# WL-FRONT.net
KiCad netlist of a schematic drawn in Altium Designer
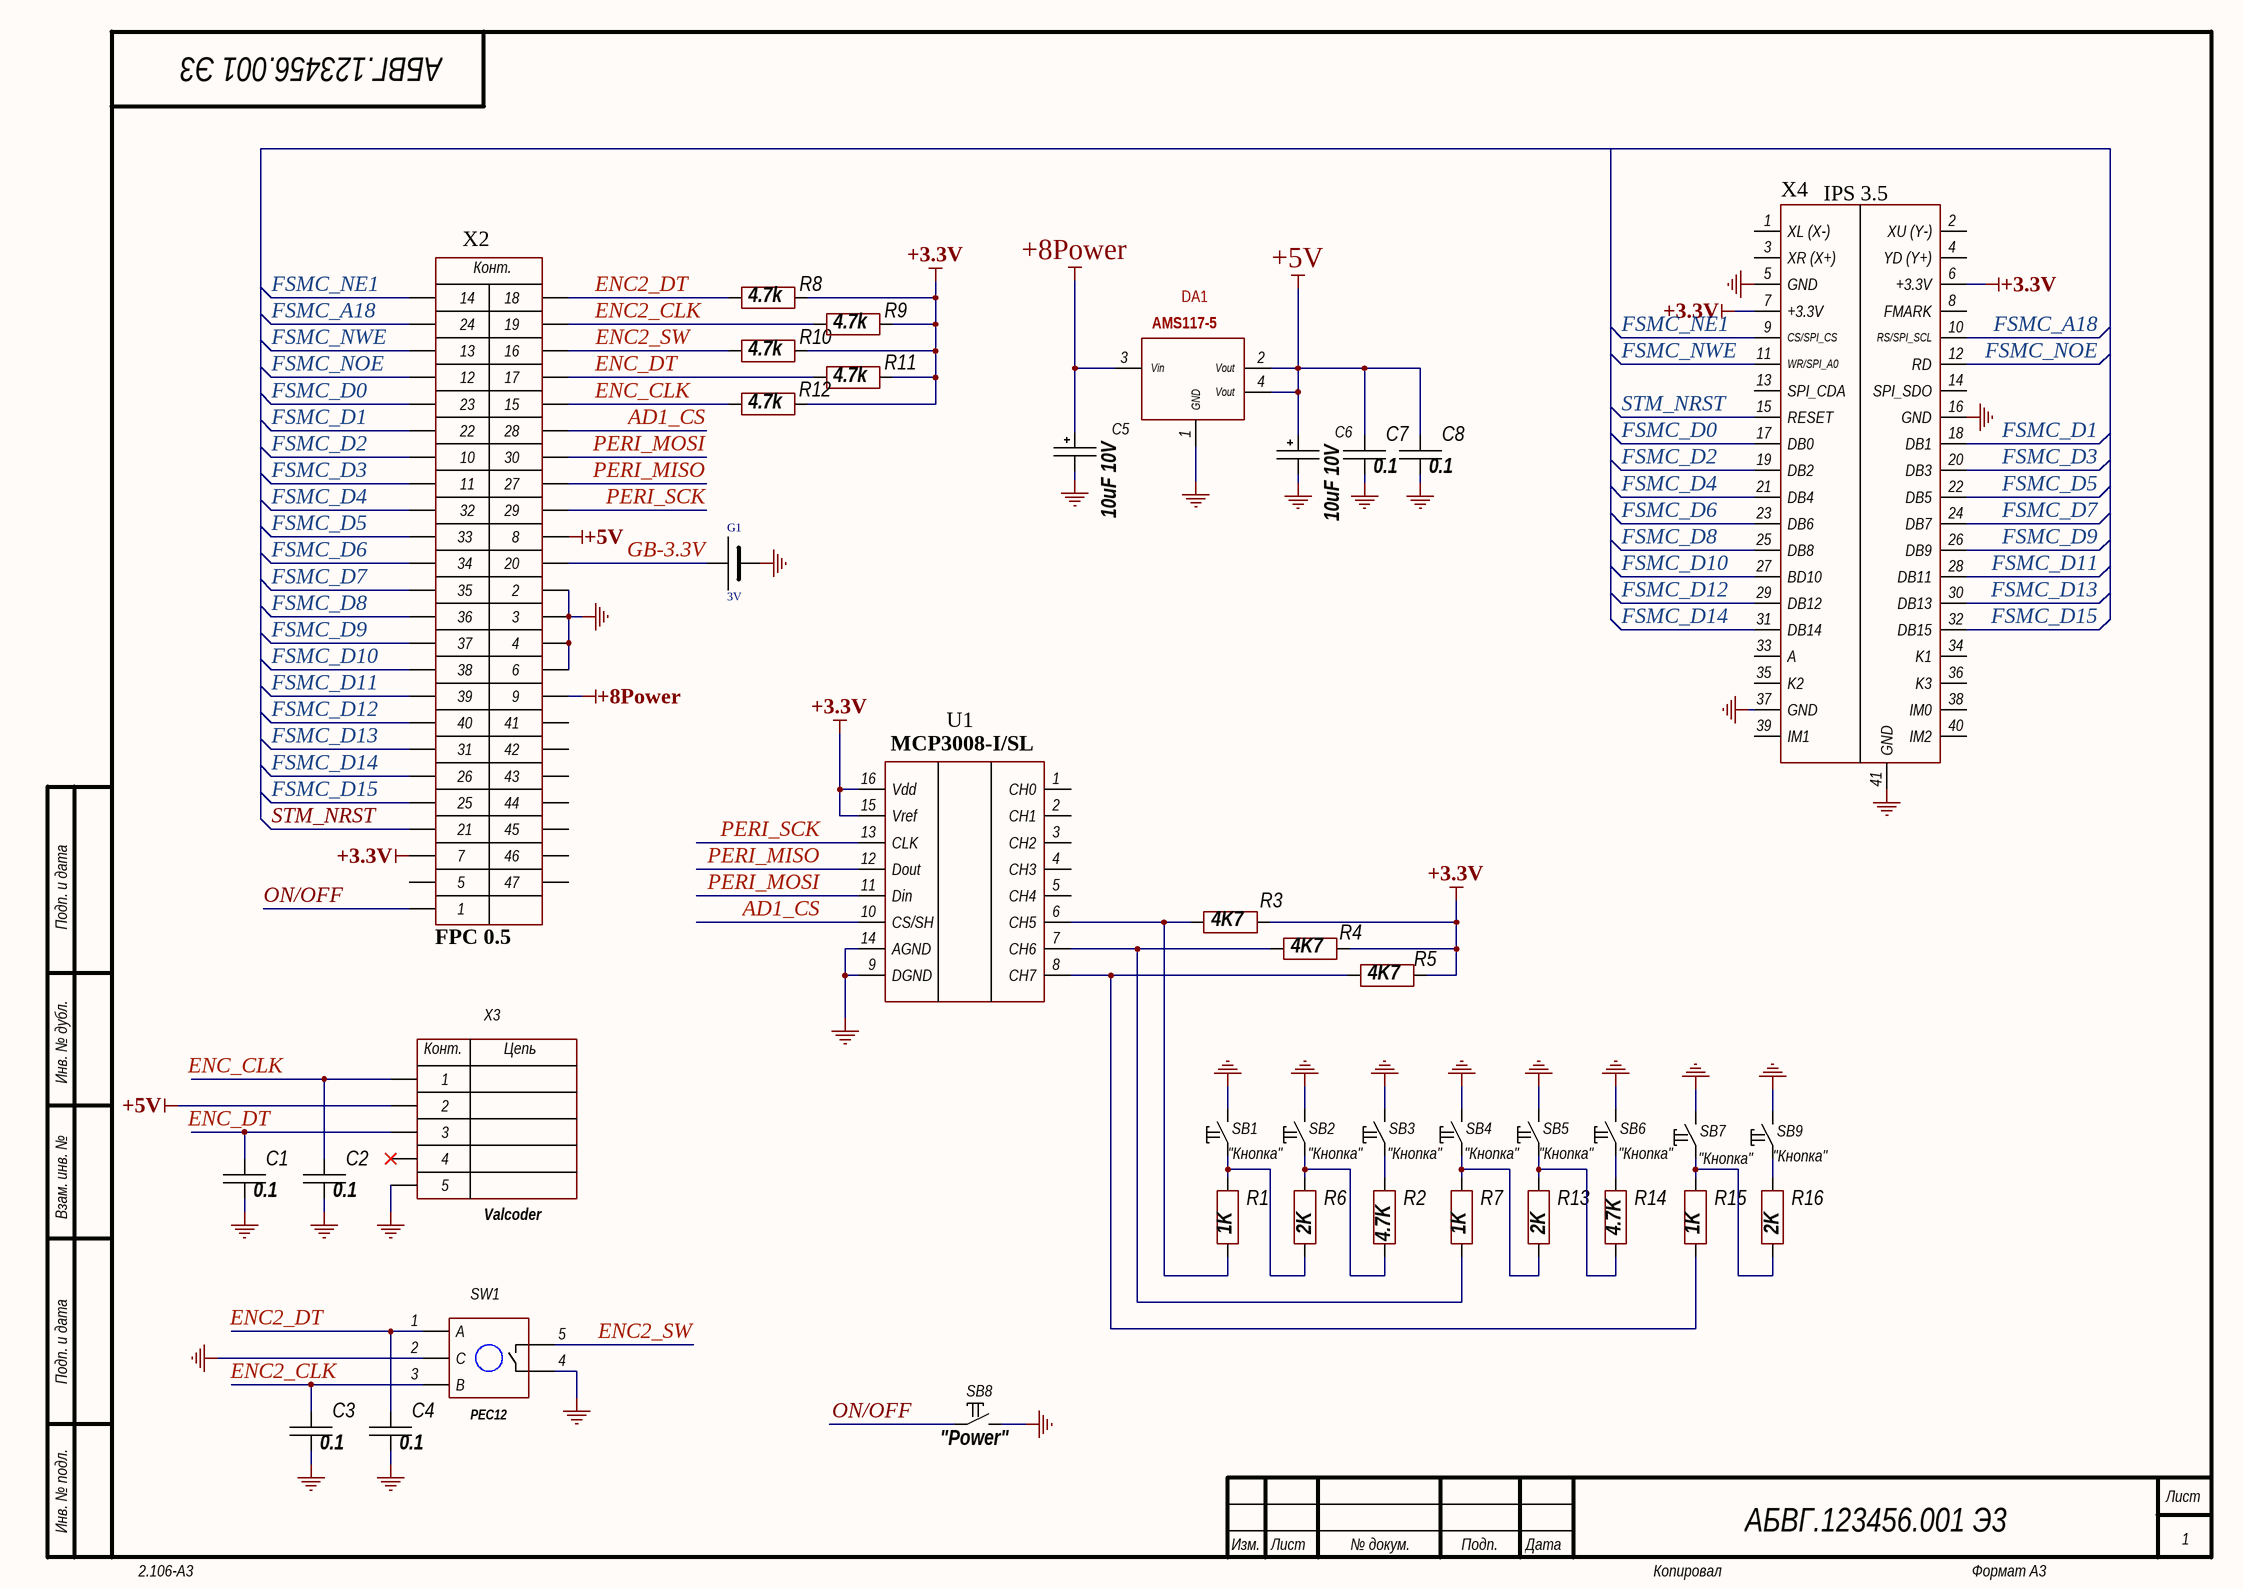
[diagram p0: WL-FRONT.SchDoc]

(export (version "E")
  (design (tool "Eeschema 10.0.6"))
  (components
    (comp (ref "C1")
      (value "0.1")
      (footprint "standard:CH0805C")
      (libsource (lib "Discrete") (part "Capacitor"))
    )
    (comp (ref "C2")
      (value "0.1")
      (footprint "standard:CH0805C")
      (libsource (lib "Discrete") (part "Capacitor"))
    )
    (comp (ref "C3")
      (value "0.1")
      (footprint "standard:CH0805C")
      (libsource (lib "Discrete") (part "Capacitor"))
    )
    (comp (ref "C4")
      (value "0.1")
      (footprint "standard:CH0805C")
      (libsource (lib "Discrete") (part "Capacitor"))
    )
    (comp (ref "C5")
      (value "10uF 10V")
      (footprint "standard:TANTAL_B")
      (libsource (lib "Discrete") (part "TantalCap"))
    )
    (comp (ref "C6")
      (value "10uF 10V")
      (footprint "standard:TANTAL_B")
      (libsource (lib "Discrete") (part "TantalCap"))
    )
    (comp (ref "C7")
      (value "0.1")
      (footprint "standard:CH0805C")
      (libsource (lib "Discrete") (part "Capacitor"))
    )
    (comp (ref "C8")
      (value "0.1")
      (footprint "standard:CH0805C")
      (libsource (lib "Discrete") (part "Capacitor"))
    )
    (comp (ref "DA1") (value "AMS117-5") (footprint "SOT223") (libsource (lib "Analog") (part "AMS117")))
    (comp (ref "G1")
      (value "3V")
      (footprint "BAT: CH224-2032")
      (libsource (lib "Connectors") (part "POWER_BAT"))
    )
    (comp (ref "R1") (value "1K") (footprint "standard:CH0805R") (libsource (lib "") (part "Resistor_2")))
    (comp (ref "R2") (value "4.7K") (footprint "standard:CH0805R") (libsource (lib "") (part "Resistor_2")))
    (comp (ref "R3")
      (value "4K7")
      (footprint "standard:CH0805R")
      (libsource (lib "Discrete") (part "Resistor"))
    )
    (comp (ref "R4") (value "4K7") (footprint "standard:CH0805R") (libsource (lib "") (part "Resistor_3")))
    (comp (ref "R5")
      (value "4K7")
      (footprint "standard:CH0805R")
      (libsource (lib "Discrete") (part "Resistor"))
    )
    (comp (ref "R6") (value "2K") (footprint "standard:CH0805R") (libsource (lib "") (part "Resistor_2")))
    (comp (ref "R7") (value "1K") (footprint "standard:CH0805R") (libsource (lib "") (part "Resistor_2")))
    (comp (ref "R8") (value "4.7k") (footprint "standard:CH0805R") (libsource (lib "") (part "Resistor_1")))
    (comp (ref "R9") (value "4.7k") (footprint "standard:CH0805R") (libsource (lib "") (part "Resistor_1")))
    (comp (ref "R10") (value "4.7k") (footprint "standard:CH0805R") (libsource (lib "") (part "Resistor_1")))
    (comp (ref "R11") (value "4.7k") (footprint "standard:CH0805R") (libsource (lib "") (part "Resistor_1")))
    (comp (ref "R12") (value "4.7k") (footprint "standard:CH0805R") (libsource (lib "") (part "Resistor_1")))
    (comp (ref "R13") (value "2K") (footprint "standard:CH0805R") (libsource (lib "") (part "Resistor_2")))
    (comp (ref "R14") (value "4.7K") (footprint "standard:CH0805R") (libsource (lib "") (part "Resistor_2")))
    (comp (ref "R15") (value "1K") (footprint "standard:CH0805R") (libsource (lib "") (part "Resistor_2")))
    (comp (ref "R16") (value "2K") (footprint "standard:CH0805R") (libsource (lib "") (part "Resistor_2")))
    (comp (ref "SB1")
      (value "\"Кнопка\"")
      (footprint "BUT: 6X6_SMD1")
      (description "6x6 mm")
      (libsource (lib "Connectors") (part "Tactile switches"))
    )
    (comp (ref "SB2")
      (value "\"Кнопка\"")
      (footprint "custom:BUT: 6x6 SMD")
      (description "6x6 mm")
      (libsource (lib "Connectors") (part "Tactile switches"))
    )
    (comp (ref "SB3")
      (value "\"Кнопка\"")
      (footprint "custom:BUT: 6x6 SMD")
      (description "6x6 mm")
      (libsource (lib "Connectors") (part "Tactile switches"))
    )
    (comp (ref "SB4")
      (value "\"Кнопка\"")
      (footprint "custom:BUT: 6x6 SMD")
      (description "6x6 mm")
      (libsource (lib "Connectors") (part "Tactile switches"))
    )
    (comp (ref "SB5")
      (value "\"Кнопка\"")
      (footprint "custom:BUT: 6x6 SMD")
      (description "6x6 mm")
      (libsource (lib "Connectors") (part "Tactile switches"))
    )
    (comp (ref "SB6")
      (value "\"Кнопка\"")
      (footprint "custom:BUT: 6x6 SMD")
      (description "6x6 mm")
      (libsource (lib "Connectors") (part "Tactile switches"))
    )
    (comp (ref "SB7")
      (value "\"Кнопка\"")
      (footprint "custom:BUT: 6x6 SMD")
      (description "6x6 mm")
      (libsource (lib "Connectors") (part "Tactile switches"))
    )
    (comp (ref "SB8")
      (value "\"Power\"")
      (footprint "custom:BUT: 6x6")
      (description "6x6 mm")
      (libsource (lib "Connectors") (part "Tactile switches"))
    )
    (comp (ref "SB9")
      (value "\"Кнопка\"")
      (footprint "custom:BUT: 6x6 SMD")
      (description "6x6 mm")
      (libsource (lib "Connectors") (part "Tactile switches"))
    )
    (comp (ref "SW1")
      (value "PEC12")
      (footprint "Valkoder-m2")
      (description "Encoder")
      (libsource (lib "Connectors") (part "PEC12"))
    )
    (comp (ref "U1")
      (value "MCP3008-I/SL")
      (footprint "16-SOIC")
      (libsource (lib "Digital") (part "MCP3008-I/SL"))
    )
    (comp (ref "X2")
      (value "FPC 0.5")
      (footprint "CON: PBD2x20")
      (libsource (lib "Connectors") (part "FPC-45-0.5"))
    )
    (comp (ref "X3")
      (value "Valcoder")
      (footprint "custom:CON: PLS-5")
      (libsource (lib "Connectors") (part "5-Connector"))
    )
    (comp (ref "X4")
      (value "IPS 3.5")
      (footprint "IPS 3.5 ILI9481")
      (libsource (lib "Digital") (part "LCD-IPS 3.5"))
    )
  )
  (nets
    (net (code "1") (name "+3.3V") (class "Default")
      (node (ref "R10") (pin "1") (pinfunction "1_1") (pintype "passive"))
      (node (ref "R11") (pin "1") (pinfunction "1_1") (pintype "passive"))
      (node (ref "R12") (pin "1") (pinfunction "1_1") (pintype "passive"))
      (node (ref "R3") (pin "2") (pinfunction "2_2") (pintype "passive"))
      (node (ref "R4") (pin "2") (pinfunction "2_2") (pintype "passive"))
      (node (ref "R5") (pin "2") (pinfunction "2_2") (pintype "passive"))
      (node (ref "R8") (pin "1") (pinfunction "1_1") (pintype "passive"))
      (node (ref "R9") (pin "1") (pinfunction "1_1") (pintype "passive"))
      (node (ref "U1") (pin "15") (pinfunction "Vref_15") (pintype "passive"))
      (node (ref "U1") (pin "16") (pinfunction "Vdd_16") (pintype "passive"))
      (node (ref "X2") (pin "7") (pinfunction "7_7") (pintype "power_in"))
      (node (ref "X4") (pin "6") (pinfunction "+3.3V_6") (pintype "passive"))
      (node (ref "X4") (pin "7") (pinfunction "+3.3V_7") (pintype "passive"))
    )
    (net (code "2") (name "+5V") (class "Default")
      (node (ref "C6") (pin "1") (pinfunction "1_1") (pintype "power_in"))
      (node (ref "C7") (pin "1") (pinfunction "1_1") (pintype "power_in"))
      (node (ref "C8") (pin "1") (pinfunction "1_1") (pintype "power_in"))
      (node (ref "DA1") (pin "2") (pinfunction "Vout_2") (pintype "passive"))
      (node (ref "DA1") (pin "4") (pinfunction "Vout_4") (pintype "passive"))
      (node (ref "X2") (pin "8") (pinfunction "8_8") (pintype "power_in"))
      (node (ref "X3") (pin "2") (pinfunction "2_2") (pintype "passive"))
    )
    (net (code "3") (name "+8Power") (class "Default")
      (node (ref "C5") (pin "1") (pinfunction "1_1") (pintype "power_in"))
      (node (ref "DA1") (pin "3") (pinfunction "Vin_3") (pintype "passive"))
      (node (ref "X2") (pin "9") (pinfunction "9_9") (pintype "power_in"))
    )
    (net (code "4") (name "/AD1_CS") (class "Default")
      (node (ref "U1") (pin "10") (pinfunction "CS/SH_10") (pintype "passive"))
      (node (ref "X2") (pin "28") (pinfunction "28_28") (pintype "power_in"))
    )
    (net (code "5") (name "/ENC2_CLK") (class "Default")
      (node (ref "C3") (pin "1") (pinfunction "1_1") (pintype "power_in"))
      (node (ref "R9") (pin "2") (pinfunction "2_2") (pintype "passive"))
      (node (ref "SW1") (pin "3") (pinfunction "B_3") (pintype "passive"))
      (node (ref "X2") (pin "19") (pinfunction "19_19") (pintype "power_in"))
    )
    (net (code "6") (name "/ENC2_DT") (class "Default")
      (node (ref "C4") (pin "1") (pinfunction "1_1") (pintype "power_in"))
      (node (ref "R8") (pin "2") (pinfunction "2_2") (pintype "passive"))
      (node (ref "SW1") (pin "1") (pinfunction "A_1") (pintype "passive"))
      (node (ref "X2") (pin "18") (pinfunction "18_18") (pintype "power_in"))
    )
    (net (code "7") (name "/ENC2_SW") (class "Default")
      (node (ref "R10") (pin "2") (pinfunction "2_2") (pintype "passive"))
      (node (ref "SW1") (pin "5") (pinfunction "5_5") (pintype "passive"))
      (node (ref "X2") (pin "16") (pinfunction "16_16") (pintype "power_in"))
    )
    (net (code "8") (name "/ENC_CLK") (class "Default")
      (node (ref "C2") (pin "1") (pinfunction "1_1") (pintype "power_in"))
      (node (ref "R12") (pin "2") (pinfunction "2_2") (pintype "passive"))
      (node (ref "X2") (pin "15") (pinfunction "15_15") (pintype "power_in"))
      (node (ref "X3") (pin "1") (pinfunction "1_1") (pintype "passive"))
    )
    (net (code "9") (name "/ENC_DT") (class "Default")
      (node (ref "C1") (pin "1") (pinfunction "1_1") (pintype "power_in"))
      (node (ref "R11") (pin "2") (pinfunction "2_2") (pintype "passive"))
      (node (ref "X2") (pin "17") (pinfunction "17_17") (pintype "power_in"))
      (node (ref "X3") (pin "3") (pinfunction "3_3") (pintype "power_in"))
    )
    (net (code "10") (name "/FSMC_A18") (class "Default")
      (node (ref "X2") (pin "24") (pinfunction "24_24") (pintype "passive"))
      (node (ref "X4") (pin "10") (pinfunction "RS/SPI_SCL_10") (pintype "passive"))
    )
    (net (code "11") (name "/FSMC_D0") (class "Default")
      (node (ref "X2") (pin "23") (pinfunction "23_23") (pintype "power_in"))
      (node (ref "X4") (pin "17") (pinfunction "DB0_17") (pintype "passive"))
    )
    (net (code "12") (name "/FSMC_D1") (class "Default")
      (node (ref "X2") (pin "22") (pinfunction "22_22") (pintype "power_in"))
      (node (ref "X4") (pin "18") (pinfunction "DB1_18") (pintype "passive"))
    )
    (net (code "13") (name "/FSMC_D2") (class "Default")
      (node (ref "X2") (pin "10") (pinfunction "10_10") (pintype "power_in"))
      (node (ref "X4") (pin "19") (pinfunction "DB2_19") (pintype "passive"))
    )
    (net (code "14") (name "/FSMC_D3") (class "Default")
      (node (ref "X2") (pin "11") (pinfunction "11_11") (pintype "power_in"))
      (node (ref "X4") (pin "20") (pinfunction "DB3_20") (pintype "passive"))
    )
    (net (code "15") (name "/FSMC_D4") (class "Default")
      (node (ref "X2") (pin "32") (pinfunction "32_32") (pintype "power_in"))
      (node (ref "X4") (pin "21") (pinfunction "DB4_21") (pintype "passive"))
    )
    (net (code "16") (name "/FSMC_D5") (class "Default")
      (node (ref "X2") (pin "33") (pinfunction "33_33") (pintype "power_in"))
      (node (ref "X4") (pin "22") (pinfunction "DB5_22") (pintype "passive"))
    )
    (net (code "17") (name "/FSMC_D6") (class "Default")
      (node (ref "X2") (pin "34") (pinfunction "34_34") (pintype "power_in"))
      (node (ref "X4") (pin "23") (pinfunction "DB6_23") (pintype "passive"))
    )
    (net (code "18") (name "/FSMC_D7") (class "Default")
      (node (ref "X2") (pin "35") (pinfunction "35_35") (pintype "power_in"))
      (node (ref "X4") (pin "24") (pinfunction "DB7_24") (pintype "passive"))
    )
    (net (code "19") (name "/FSMC_D8") (class "Default")
      (node (ref "X2") (pin "36") (pinfunction "36_36") (pintype "power_in"))
      (node (ref "X4") (pin "25") (pinfunction "DB8_25") (pintype "passive"))
    )
    (net (code "20") (name "/FSMC_D9") (class "Default")
      (node (ref "X2") (pin "37") (pinfunction "37_37") (pintype "power_in"))
      (node (ref "X4") (pin "26") (pinfunction "DB9_26") (pintype "passive"))
    )
    (net (code "21") (name "/FSMC_D10") (class "Default")
      (node (ref "X2") (pin "38") (pinfunction "38_38") (pintype "power_in"))
      (node (ref "X4") (pin "27") (pinfunction "BD10_27") (pintype "passive"))
    )
    (net (code "22") (name "/FSMC_D11") (class "Default")
      (node (ref "X2") (pin "39") (pinfunction "39_39") (pintype "power_in"))
      (node (ref "X4") (pin "28") (pinfunction "DB11_28") (pintype "passive"))
    )
    (net (code "23") (name "/FSMC_D12") (class "Default")
      (node (ref "X2") (pin "40") (pinfunction "40_40") (pintype "power_in"))
      (node (ref "X4") (pin "29") (pinfunction "DB12_29") (pintype "passive"))
    )
    (net (code "24") (name "/FSMC_D13") (class "Default")
      (node (ref "X2") (pin "31") (pinfunction "31_31") (pintype "power_in"))
      (node (ref "X4") (pin "30") (pinfunction "DB13_30") (pintype "passive"))
    )
    (net (code "25") (name "/FSMC_D14") (class "Default")
      (node (ref "X2") (pin "26") (pinfunction "26_26") (pintype "power_in"))
      (node (ref "X4") (pin "31") (pinfunction "DB14_31") (pintype "passive"))
    )
    (net (code "26") (name "/FSMC_D15") (class "Default")
      (node (ref "X2") (pin "25") (pinfunction "25_25") (pintype "power_in"))
      (node (ref "X4") (pin "32") (pinfunction "DB15_32") (pintype "passive"))
    )
    (net (code "27") (name "/FSMC_NE1") (class "Default")
      (node (ref "X2") (pin "14") (pinfunction "14_14") (pintype "passive"))
      (node (ref "X4") (pin "9") (pinfunction "CS/SPI_CS_9") (pintype "passive"))
    )
    (net (code "28") (name "/FSMC_NOE") (class "Default")
      (node (ref "X2") (pin "12") (pinfunction "12_12") (pintype "power_in"))
      (node (ref "X4") (pin "12") (pinfunction "RD_12") (pintype "passive"))
    )
    (net (code "29") (name "/FSMC_NWE") (class "Default")
      (node (ref "X2") (pin "13") (pinfunction "13_13") (pintype "power_in"))
      (node (ref "X4") (pin "11") (pinfunction "WR/SPI_A0_11") (pintype "passive"))
    )
    (net (code "30") (name "/GB-3.3V") (class "Default")
      (node (ref "G1") (pin "1") (pinfunction "0_1") (pintype "passive"))
      (node (ref "X2") (pin "20") (pinfunction "20_20") (pintype "power_in"))
    )
    (net (code "31") (name "/ON{slash}OFF") (class "Default")
      (node (ref "SB8") (pin "1") (pinfunction "1_1") (pintype "passive"))
      (node (ref "X2") (pin "1") (pinfunction "1_1") (pintype "power_in"))
    )
    (net (code "32") (name "/PERI_MISO") (class "Default")
      (node (ref "U1") (pin "12") (pinfunction "Dout_12") (pintype "passive"))
      (node (ref "X2") (pin "27") (pinfunction "27_27") (pintype "power_in"))
    )
    (net (code "33") (name "/PERI_MOSI") (class "Default")
      (node (ref "U1") (pin "11") (pinfunction "Din_11") (pintype "passive"))
      (node (ref "X2") (pin "30") (pinfunction "30_30") (pintype "power_in"))
    )
    (net (code "34") (name "/PERI_SCK") (class "Default")
      (node (ref "U1") (pin "13") (pinfunction "CLK_13") (pintype "passive"))
      (node (ref "X2") (pin "29") (pinfunction "29_29") (pintype "power_in"))
    )
    (net (code "35") (name "/STM_NRST") (class "Default")
      (node (ref "X2") (pin "21") (pinfunction "21_21") (pintype "power_in"))
      (node (ref "X4") (pin "15") (pinfunction "RESET_15") (pintype "passive"))
    )
    (net (code "36") (name "GND") (class "Default")
      (node (ref "C1") (pin "2") (pinfunction "2_2") (pintype "power_in"))
      (node (ref "C2") (pin "2") (pinfunction "2_2") (pintype "power_in"))
      (node (ref "C3") (pin "2") (pinfunction "2_2") (pintype "power_in"))
      (node (ref "C4") (pin "2") (pinfunction "2_2") (pintype "power_in"))
      (node (ref "C5") (pin "2") (pinfunction "2_2") (pintype "power_in"))
      (node (ref "C6") (pin "2") (pinfunction "2_2") (pintype "power_in"))
      (node (ref "C7") (pin "2") (pinfunction "2_2") (pintype "power_in"))
      (node (ref "C8") (pin "2") (pinfunction "2_2") (pintype "power_in"))
      (node (ref "DA1") (pin "1") (pinfunction "GND_1") (pintype "passive"))
      (node (ref "G1") (pin "2") (pinfunction "1_2") (pintype "passive"))
      (node (ref "SB1") (pin "2") (pinfunction "2_2") (pintype "passive"))
      (node (ref "SB2") (pin "2") (pinfunction "2_2") (pintype "passive"))
      (node (ref "SB3") (pin "2") (pinfunction "2_2") (pintype "passive"))
      (node (ref "SB4") (pin "2") (pinfunction "2_2") (pintype "passive"))
      (node (ref "SB5") (pin "2") (pinfunction "2_2") (pintype "passive"))
      (node (ref "SB6") (pin "2") (pinfunction "2_2") (pintype "passive"))
      (node (ref "SB7") (pin "2") (pinfunction "2_2") (pintype "passive"))
      (node (ref "SB8") (pin "2") (pinfunction "2_2") (pintype "passive"))
      (node (ref "SB9") (pin "2") (pinfunction "2_2") (pintype "passive"))
      (node (ref "SW1") (pin "2") (pinfunction "C_2") (pintype "passive"))
      (node (ref "SW1") (pin "4") (pinfunction "4_4") (pintype "passive"))
      (node (ref "U1") (pin "14") (pinfunction "AGND_14") (pintype "passive"))
      (node (ref "U1") (pin "9") (pinfunction "DGND_9") (pintype "passive"))
      (node (ref "X2") (pin "2") (pinfunction "2_2") (pintype "power_in"))
      (node (ref "X2") (pin "3") (pinfunction "3_3") (pintype "power_in"))
      (node (ref "X2") (pin "4") (pinfunction "4_4") (pintype "power_in"))
      (node (ref "X2") (pin "6") (pinfunction "6_6") (pintype "power_in"))
      (node (ref "X3") (pin "5") (pinfunction "5_5") (pintype "power_in"))
      (node (ref "X4") (pin "16") (pinfunction "GND_16") (pintype "passive"))
      (node (ref "X4") (pin "37") (pinfunction "GND_37") (pintype "passive"))
      (node (ref "X4") (pin "41") (pinfunction "GND_41") (pintype "passive"))
      (node (ref "X4") (pin "5") (pinfunction "GND_5") (pintype "passive"))
    )
    (net (code "37") (name "Net-(R1-Pad2)") (class "Default")
      (node (ref "R1") (pin "2") (pinfunction "2_2") (pintype "passive"))
      (node (ref "R6") (pin "1") (pinfunction "1_1") (pintype "passive"))
      (node (ref "SB1") (pin "1") (pinfunction "1_1") (pintype "passive"))
    )
    (net (code "38") (name "Net-(R2-Pad1)") (class "Default")
      (node (ref "R2") (pin "1") (pinfunction "1_1") (pintype "passive"))
      (node (ref "R6") (pin "2") (pinfunction "2_2") (pintype "passive"))
      (node (ref "SB2") (pin "1") (pinfunction "1_1") (pintype "passive"))
    )
    (net (code "39") (name "Net-(R2-Pad2)") (class "Default")
      (node (ref "R2") (pin "2") (pinfunction "2_2") (pintype "passive"))
      (node (ref "SB3") (pin "1") (pinfunction "1_1") (pintype "passive"))
    )
    (net (code "40") (name "Net-(R13-Pad1)") (class "Default")
      (node (ref "R13") (pin "1") (pinfunction "1_1") (pintype "passive"))
      (node (ref "R7") (pin "2") (pinfunction "2_2") (pintype "passive"))
      (node (ref "SB4") (pin "1") (pinfunction "1_1") (pintype "passive"))
    )
    (net (code "41") (name "Net-(R13-Pad2)") (class "Default")
      (node (ref "R13") (pin "2") (pinfunction "2_2") (pintype "passive"))
      (node (ref "R14") (pin "1") (pinfunction "1_1") (pintype "passive"))
      (node (ref "SB5") (pin "1") (pinfunction "1_1") (pintype "passive"))
    )
    (net (code "42") (name "Net-(R14-Pad2)") (class "Default")
      (node (ref "R14") (pin "2") (pinfunction "2_2") (pintype "passive"))
      (node (ref "SB6") (pin "1") (pinfunction "1_1") (pintype "passive"))
    )
    (net (code "43") (name "Net-(R15-Pad2)") (class "Default")
      (node (ref "R15") (pin "2") (pinfunction "2_2") (pintype "passive"))
      (node (ref "R16") (pin "1") (pinfunction "1_1") (pintype "passive"))
      (node (ref "SB7") (pin "1") (pinfunction "1_1") (pintype "passive"))
    )
    (net (code "44") (name "Net-(R16-Pad2)") (class "Default")
      (node (ref "R16") (pin "2") (pinfunction "2_2") (pintype "passive"))
      (node (ref "SB9") (pin "1") (pinfunction "1_1") (pintype "passive"))
    )
    (net (code "45") (name "Net-(U1-CH5)") (class "Default")
      (node (ref "R1") (pin "1") (pinfunction "1_1") (pintype "passive"))
      (node (ref "R3") (pin "1") (pinfunction "1_1") (pintype "passive"))
      (node (ref "U1") (pin "6") (pinfunction "CH5_6") (pintype "passive"))
    )
    (net (code "46") (name "Net-(U1-CH6)") (class "Default")
      (node (ref "R4") (pin "1") (pinfunction "1_1") (pintype "passive"))
      (node (ref "R7") (pin "1") (pinfunction "1_1") (pintype "passive"))
      (node (ref "U1") (pin "7") (pinfunction "CH6_7") (pintype "passive"))
    )
    (net (code "47") (name "Net-(U1-CH7)") (class "Default")
      (node (ref "R15") (pin "1") (pinfunction "1_1") (pintype "passive"))
      (node (ref "R5") (pin "1") (pinfunction "1_1") (pintype "passive"))
      (node (ref "U1") (pin "8") (pinfunction "CH7_8") (pintype "passive"))
    )
    (net (code "48") (name "unconnected-(U1-CH0-Pad1)") (class "Default")
      (node (ref "U1") (pin "1") (pinfunction "CH0_1") (pintype "passive"))
    )
    (net (code "49") (name "unconnected-(U1-CH1-Pad2)") (class "Default")
      (node (ref "U1") (pin "2") (pinfunction "CH1_2") (pintype "passive"))
    )
    (net (code "50") (name "unconnected-(U1-CH2-Pad3)") (class "Default")
      (node (ref "U1") (pin "3") (pinfunction "CH2_3") (pintype "passive"))
    )
    (net (code "51") (name "unconnected-(U1-CH3-Pad4)") (class "Default")
      (node (ref "U1") (pin "4") (pinfunction "CH3_4") (pintype "passive"))
    )
    (net (code "52") (name "unconnected-(U1-CH4-Pad5)") (class "Default")
      (node (ref "U1") (pin "5") (pinfunction "CH4_5") (pintype "passive"))
    )
    (net (code "53") (name "unconnected-(X2-Pad5)") (class "Default")
      (node (ref "X2") (pin "5") (pinfunction "5_5") (pintype "power_in"))
    )
    (net (code "54") (name "unconnected-(X2-Pad41)") (class "Default")
      (node (ref "X2") (pin "41") (pinfunction "41_41") (pintype "power_in"))
    )
    (net (code "55") (name "unconnected-(X2-Pad42)") (class "Default")
      (node (ref "X2") (pin "42") (pinfunction "42_42") (pintype "power_in"))
    )
    (net (code "56") (name "unconnected-(X2-Pad43)") (class "Default")
      (node (ref "X2") (pin "43") (pinfunction "43_43") (pintype "power_in"))
    )
    (net (code "57") (name "unconnected-(X2-Pad44)") (class "Default")
      (node (ref "X2") (pin "44") (pinfunction "44_44") (pintype "power_in"))
    )
    (net (code "58") (name "unconnected-(X2-Pad45)") (class "Default")
      (node (ref "X2") (pin "45") (pinfunction "45_45") (pintype "power_in"))
    )
    (net (code "59") (name "unconnected-(X2-Pad46)") (class "Default")
      (node (ref "X2") (pin "46") (pinfunction "46_46") (pintype "power_in"))
    )
    (net (code "60") (name "unconnected-(X2-Pad47)") (class "Default")
      (node (ref "X2") (pin "47") (pinfunction "47_47") (pintype "power_in"))
    )
    (net (code "61") (name "unconnected-(X3-Pad4)") (class "Default")
      (node (ref "X3") (pin "4") (pinfunction "4_4") (pintype "power_in+no_connect"))
    )
    (net (code "62") (name "unconnected-(X4-A-Pad33)") (class "Default")
      (node (ref "X4") (pin "33") (pinfunction "A_33") (pintype "passive"))
    )
    (net (code "63") (name "unconnected-(X4-FMARK-Pad8)") (class "Default")
      (node (ref "X4") (pin "8") (pinfunction "FMARK_8") (pintype "passive"))
    )
    (net (code "64") (name "unconnected-(X4-IM0-Pad38)") (class "Default")
      (node (ref "X4") (pin "38") (pinfunction "IM0_38") (pintype "passive"))
    )
    (net (code "65") (name "unconnected-(X4-IM1-Pad39)") (class "Default")
      (node (ref "X4") (pin "39") (pinfunction "IM1_39") (pintype "passive"))
    )
    (net (code "66") (name "unconnected-(X4-IM2-Pad40)") (class "Default")
      (node (ref "X4") (pin "40") (pinfunction "IM2_40") (pintype "passive"))
    )
    (net (code "67") (name "unconnected-(X4-K1-Pad34)") (class "Default")
      (node (ref "X4") (pin "34") (pinfunction "K1_34") (pintype "passive"))
    )
    (net (code "68") (name "unconnected-(X4-K2-Pad35)") (class "Default")
      (node (ref "X4") (pin "35") (pinfunction "K2_35") (pintype "passive"))
    )
    (net (code "69") (name "unconnected-(X4-K3-Pad36)") (class "Default")
      (node (ref "X4") (pin "36") (pinfunction "K3_36") (pintype "passive"))
    )
    (net (code "70") (name "unconnected-(X4-SPI_CDA-Pad13)") (class "Default")
      (node (ref "X4") (pin "13") (pinfunction "SPI_CDA_13") (pintype "passive"))
    )
    (net (code "71") (name "unconnected-(X4-SPI_SDO-Pad14)") (class "Default")
      (node (ref "X4") (pin "14") (pinfunction "SPI_SDO_14") (pintype "passive"))
    )
    (net (code "72") (name "unconnected-(X4-XL_(X-)-Pad1)") (class "Default")
      (node (ref "X4") (pin "1") (pinfunction "XL_(X-)_1") (pintype "passive"))
    )
    (net (code "73") (name "unconnected-(X4-XR_(X+)-Pad3)") (class "Default")
      (node (ref "X4") (pin "3") (pinfunction "XR_(X+)_3") (pintype "passive"))
    )
    (net (code "74") (name "unconnected-(X4-XU_(Y-)-Pad2)") (class "Default")
      (node (ref "X4") (pin "2") (pinfunction "XU_(Y-)_2") (pintype "passive"))
    )
    (net (code "75") (name "unconnected-(X4-YD_(Y+)-Pad4)") (class "Default")
      (node (ref "X4") (pin "4") (pinfunction "YD_(Y+)_4") (pintype "passive"))
    )
  )
)
